# PowerSupply.net
KiCad netlist of a schematic drawn in Altium Designer
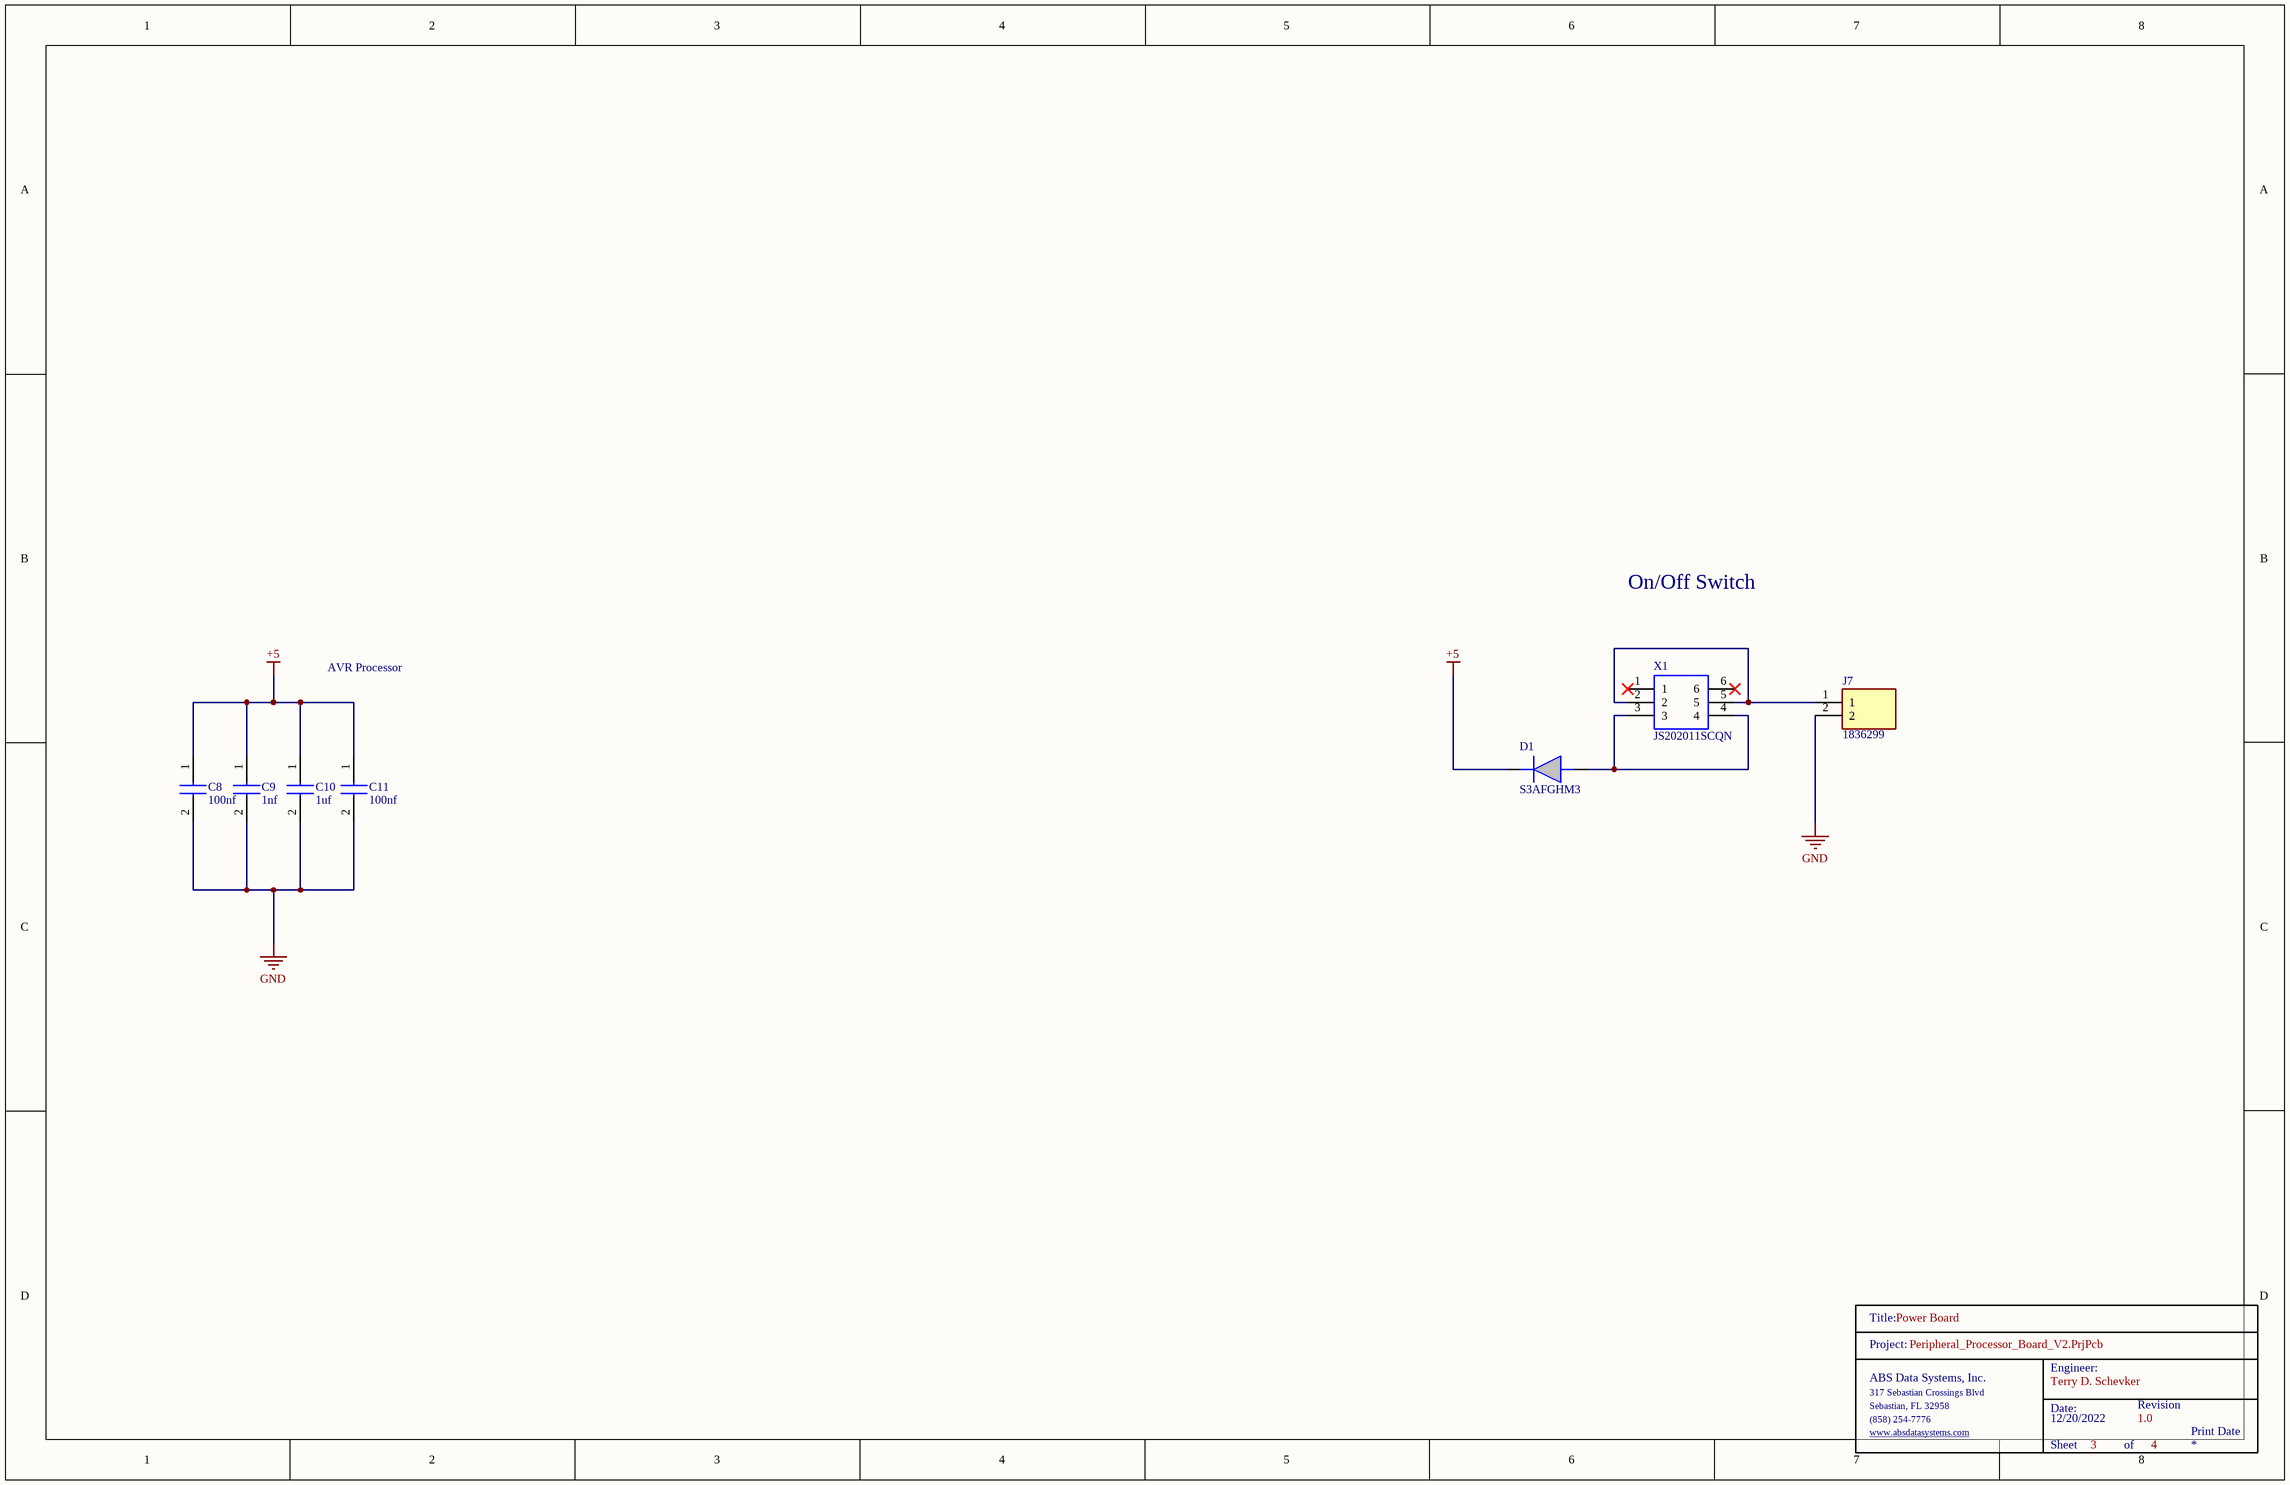
[diagram p0: PowerSupply.SchDoc]

(export (version "E")
  (design (tool "Eeschema 10.0.6"))
  (components
    (comp (ref "C8")
      (value "100nf")
      (footprint "0603")
      (description "Samsung Electro-Mechanics 0603 100nf")
      (libsource (lib "Capacitors") (part "CL10B104JB8NNNC"))
    )
    (comp (ref "C9")
      (value "1nf")
      (footprint "0603")
      (description "Samsung Electro-Mechanics 0603 1nf")
      (libsource (lib "Capacitors") (part "CL10B102KB8NNNL"))
    )
    (comp (ref "C10")
      (value "1uf")
      (footprint "0603")
      (description "Samsung Electro-Mechanics 0603 1uf")
      (libsource (lib "Capacitors") (part "CL10B105KA8NNNL"))
    )
    (comp (ref "C11")
      (value "100nf")
      (footprint "0603")
      (description "Samsung Electro-Mechanics 0603 100nf")
      (libsource (lib "Capacitors") (part "CL10B104JB8NNNC"))
    )
    (comp (ref "D1")
      (value "S3AFGHM3")
      (footprint "DO-221AC")
      (description "Rectifiers VR=400V, IO=3A")
      (fields
        (field (name "MOUSER PART NUMBER") "750-1N4001-G")
        (field (name "MANUFACTURER_PART_NUMBER") "1N4001-G")
      )
      (libsource (lib "SemiConductors") (part "S3AFGHM3/I"))
    )
    (comp (ref "J7")
      (value "1836299")
      (footprint "Connectors:1836299")
      (description "Phoenix Contact MCV Series, 5.08mm Pitch 2 Way Base Strip, Solder Termination, 8A")
      (fields (field (name "MOUSER PART NUMBER") "651-1836299"))
      (libsource (lib "Connectors") (part "1836299"))
    )
    (comp (ref "TitleBlock_4") (value "TitleBlock") (libsource (lib "Misc") (part "TitleBlock")))
    (comp (ref "X1")
      (value "JS202011SCQN")
      (footprint "JS202011SCQN")
      (description "Sub miniature slide switches")
      (fields (field (name "MOUSER PART NUMBER") "611-JS202011SCQN"))
      (libsource (lib "Misc") (part "JS202011SCQN"))
    )
  )
  (nets
    (net (code "1") (name "+5") (class "Default")
      (node (ref "C10") (pin "1") (pinfunction "1_1") (pintype "passive"))
      (node (ref "C11") (pin "1") (pinfunction "1_1") (pintype "passive"))
      (node (ref "C8") (pin "1") (pinfunction "1_1") (pintype "passive"))
      (node (ref "C9") (pin "1") (pinfunction "1_1") (pintype "passive"))
      (node (ref "D1") (pin "1") (pinfunction "K_1") (pintype "passive"))
    )
    (net (code "2") (name "GND") (class "Default")
      (node (ref "C10") (pin "2") (pinfunction "2_2") (pintype "passive"))
      (node (ref "C11") (pin "2") (pinfunction "2_2") (pintype "passive"))
      (node (ref "C8") (pin "2") (pinfunction "2_2") (pintype "passive"))
      (node (ref "C9") (pin "2") (pinfunction "2_2") (pintype "passive"))
      (node (ref "J7") (pin "2") (pinfunction "2_2") (pintype "passive"))
    )
    (net (code "3") (name "Net-(D1-A)") (class "Default")
      (node (ref "D1") (pin "2") (pinfunction "A_2") (pintype "passive"))
      (node (ref "X1") (pin "3") (pinfunction "3_3") (pintype "passive"))
      (node (ref "X1") (pin "4") (pinfunction "4_4") (pintype "passive"))
    )
    (net (code "4") (name "Net-(J7-Pad1)") (class "Default")
      (node (ref "J7") (pin "1") (pinfunction "1_1") (pintype "passive"))
      (node (ref "X1") (pin "2") (pinfunction "2_2") (pintype "passive"))
      (node (ref "X1") (pin "5") (pinfunction "5_5") (pintype "passive"))
    )
    (net (code "5") (name "unconnected-(X1-Pad1)") (class "Default")
      (node (ref "X1") (pin "1") (pinfunction "1_1") (pintype "passive+no_connect"))
    )
    (net (code "6") (name "unconnected-(X1-Pad6)") (class "Default")
      (node (ref "X1") (pin "6") (pinfunction "6_6") (pintype "passive+no_connect"))
    )
  )
)
